# I2C.net
KiCad netlist of a schematic drawn in Altium Designer
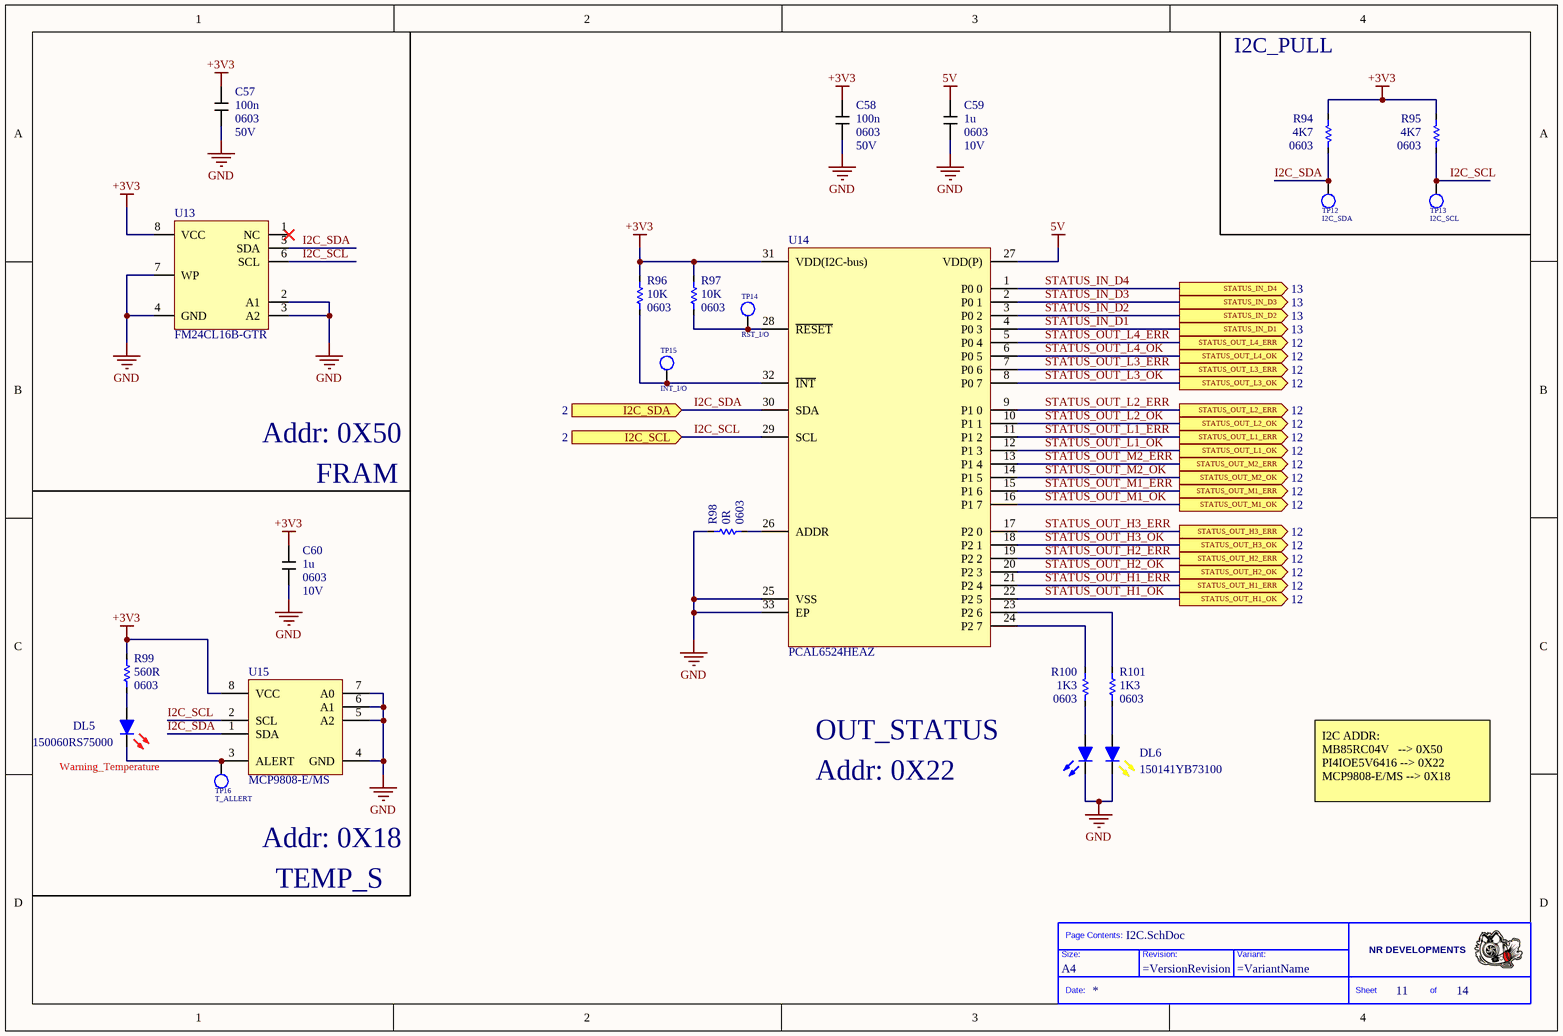
[diagram p0: I2C.SchDoc]

(export (version "E")
  (design (tool "Eeschema 10.0.6"))
  (components
    (comp (ref "C57")
      (value "100n")
      (footprint "CAPC1608X09M")
      (fields
        (field (name "CASE") "0603")
        (field (name "VOLTAGE") "50V")
        (field (name "MANUFACTURER") "KEMET")
        (field (name "PARTNUMBER") "C0603C104K5RACTU")
        (field (name "Comment") "CAP")
      )
      (libsource (lib "My_LIB") (part "CAP"))
    )
    (comp (ref "C58")
      (value "100n")
      (footprint "CAPC1608X09M")
      (fields
        (field (name "CASE") "0603")
        (field (name "VOLTAGE") "50V")
        (field (name "MANUFACTURER") "KEMET")
        (field (name "PARTNUMBER") "C0603C104K5RACTU")
        (field (name "Comment") "CAP")
      )
      (libsource (lib "My_LIB") (part "CAP"))
    )
    (comp (ref "C59")
      (value "1u")
      (footprint "CAPC1608X09M")
      (fields
        (field (name "CASE") "0603")
        (field (name "VOLTAGE") "10V")
        (field (name "MANUFACTURER") "KEMET")
        (field (name "PARTNUMBER") "C0603C105K8RACTU")
        (field (name "Comment") "CAP")
      )
      (libsource (lib "My_LIB") (part "CAP"))
    )
    (comp (ref "C60")
      (value "1u")
      (footprint "CAPC1608X09M")
      (fields
        (field (name "CASE") "0603")
        (field (name "VOLTAGE") "10V")
        (field (name "MANUFACTURER") "KEMET")
        (field (name "PARTNUMBER") "C0603C105K8RACTU")
        (field (name "Comment") "CAP")
      )
      (libsource (lib "My_LIB") (part "CAP"))
    )
    (comp (ref "DL5")
      (value "150060RS75000")
      (footprint "LED0603")
      (fields (field (name "MANUFACTURER") "Wurth Elektronik") (field (name "Comment") "LED_Red"))
      (libsource (lib "My_LIB") (part "LED_Red"))
    )
    (comp (ref "DL6")
      (value "150141YB73100")
      (footprint "WURTH-SBTW_3528")
      (description "Led Yellow - Blue 3528")
      (fields (field (name "MANUFACTURER") "Wurth") (field (name "Comment") "LED_Yellow_Blue"))
      (libsource (lib "My_LIB") (part "LED_Yellow_Blue"))
    )
    (comp (ref "R94")
      (value "4K7")
      (footprint "RESC1608X06M")
      (fields
        (field (name "CASE") "0603")
        (field (name "MANUFACTURER") "Vishay")
        (field (name "PARTNUMBER") "CRCW06034K70FKEB")
        (field (name "Comment") "Res")
      )
      (libsource (lib "My_LIB") (part "Resistor"))
    )
    (comp (ref "R95")
      (value "4K7")
      (footprint "RESC1608X06M")
      (fields
        (field (name "CASE") "0603")
        (field (name "MANUFACTURER") "Vishay")
        (field (name "PARTNUMBER") "CRCW06034K70FKEB")
        (field (name "Comment") "Res")
      )
      (libsource (lib "My_LIB") (part "Resistor"))
    )
    (comp (ref "R96")
      (value "10K")
      (footprint "RESC1608X06M")
      (fields
        (field (name "CASE") "0603")
        (field (name "MANUFACTURER") "Vishay")
        (field (name "PARTNUMBER") "CRCW060310K0FKEA")
        (field (name "Comment") "Res")
      )
      (libsource (lib "My_LIB") (part "Resistor"))
    )
    (comp (ref "R97")
      (value "10K")
      (footprint "RESC1608X06M")
      (fields
        (field (name "CASE") "0603")
        (field (name "MANUFACTURER") "Vishay")
        (field (name "PARTNUMBER") "CRCW060310K0FKEA")
        (field (name "Comment") "Res")
      )
      (libsource (lib "My_LIB") (part "Resistor"))
    )
    (comp (ref "R98")
      (value "0R")
      (footprint "RESC1608X06M")
      (fields
        (field (name "CASE") "0603")
        (field (name "MANUFACTURER") "Vishay")
        (field (name "PARTNUMBER") "CRCW06030000Z0EAC")
        (field (name "Comment") "Res")
      )
      (libsource (lib "My_LIB") (part "Resistor"))
    )
    (comp (ref "R99")
      (value "560R")
      (footprint "RESC1608X06M")
      (fields
        (field (name "CASE") "0603")
        (field (name "MANUFACTURER") "Vishay")
        (field (name "PARTNUMBER") "RC0603FR-07560RL")
        (field (name "Comment") "Res")
      )
      (libsource (lib "My_LIB") (part "Resistor"))
    )
    (comp (ref "R100")
      (value "1K3")
      (footprint "RESC1608X06M")
      (fields
        (field (name "CASE") "0603")
        (field (name "MANUFACTURER") "Vishay")
        (field (name "PARTNUMBER") "RC0603FR-071K3L")
        (field (name "Comment") "Res")
      )
      (libsource (lib "My_LIB") (part "Resistor"))
    )
    (comp (ref "R101")
      (value "1K3")
      (footprint "RESC1608X06M")
      (fields
        (field (name "CASE") "0603")
        (field (name "MANUFACTURER") "Vishay")
        (field (name "PARTNUMBER") "RC0603FR-071K3L")
        (field (name "Comment") "Res")
      )
      (libsource (lib "My_LIB") (part "Resistor"))
    )
    (comp (ref "TP12") (value "I2C_SDA") (footprint "TP_c200") (libsource (lib "My_LIB") (part "Test_Point")))
    (comp (ref "TP13") (value "I2C_SCL") (footprint "TP_c200") (libsource (lib "My_LIB") (part "Test_Point")))
    (comp (ref "TP14") (value "RST_I/O") (footprint "TP_c200") (libsource (lib "My_LIB") (part "Test_Point")))
    (comp (ref "TP15") (value "INT_I/O") (footprint "TP_c200") (libsource (lib "My_LIB") (part "Test_Point")))
    (comp (ref "TP16")
      (value "T_ALLERT")
      (footprint "TP_c200")
      (libsource (lib "My_LIB") (part "Test_Point"))
    )
    (comp (ref "U13")
      (value "FM24CL16B-GTR")
      (footprint "SOIC127P600X175-8N")
      (description "F-RAM 4kbit FRAM, I2C, 3.0V 5.5V - SOP8 T&R")
      (fields (field (name "MANUFACTURER") "Infineon Technologies") (field (name "Comment") "MB85RC04V"))
      (libsource (lib "My_LIB") (part "MB85RC04V"))
    )
    (comp (ref "U14")
      (value "PCAL6524HEAZ")
      (footprint "FP-SOT1426-1-IPC_A")
      (description "IC EXPANDER 24B 32HUQFN")
      (fields (field (name "MANUFACTURER") "NXP Semiconductors"))
      (libsource (lib "My_LIB") (part "PCAL6524HEAZ"))
    )
    (comp (ref "U15")
      (value "MCP9808-E/MS")
      (footprint "MCHP-MSOP-MS8_N")
      (fields (field (name "PARTNUMBER") "MCP9808-E/MS") (field (name "MANUFACTURER") "Microchip"))
      (libsource (lib "My_LIB") (part "MCP9808-E/MS"))
    )
  )
  (nets
    (net (code "1") (name "+3V3") (class "Default")
      (node (ref "C57") (pin "1") (pinfunction "1_1") (pintype "passive"))
      (node (ref "C58") (pin "1") (pinfunction "1_1") (pintype "passive"))
      (node (ref "C60") (pin "1") (pinfunction "1_1") (pintype "passive"))
      (node (ref "R94") (pin "2") (pinfunction "2_2") (pintype "passive"))
      (node (ref "R95") (pin "2") (pinfunction "2_2") (pintype "passive"))
      (node (ref "R96") (pin "2") (pinfunction "2_2") (pintype "passive"))
      (node (ref "R97") (pin "2") (pinfunction "2_2") (pintype "passive"))
      (node (ref "R99") (pin "2") (pinfunction "2_2") (pintype "passive"))
      (node (ref "U13") (pin "8") (pinfunction "VCC_8") (pintype "power_in"))
      (node (ref "U14") (pin "31") (pinfunction "VDD(I2C-bus)_31") (pintype "power_in"))
      (node (ref "U15") (pin "8") (pinfunction "VCC_8") (pintype "power_in"))
    )
    (net (code "2") (name "/I2C_SCL") (class "Default")
      (node (ref "R95") (pin "1") (pinfunction "1_1") (pintype "passive"))
      (node (ref "TP13") (pin "1") (pinfunction "1_1") (pintype "passive"))
      (node (ref "U13") (pin "6") (pinfunction "SCL_6") (pintype "passive"))
      (node (ref "U14") (pin "29") (pinfunction "SCL_29") (pintype "passive"))
      (node (ref "U15") (pin "2") (pinfunction "SCL_2") (pintype "passive"))
    )
    (net (code "3") (name "/I2C_SDA") (class "Default")
      (node (ref "R94") (pin "1") (pinfunction "1_1") (pintype "passive"))
      (node (ref "TP12") (pin "1") (pinfunction "1_1") (pintype "passive"))
      (node (ref "U13") (pin "5") (pinfunction "SDA_5") (pintype "passive"))
      (node (ref "U14") (pin "30") (pinfunction "SDA_30") (pintype "passive"))
      (node (ref "U15") (pin "1") (pinfunction "SDA_1") (pintype "passive"))
    )
    (net (code "4") (name "/STATUS_IN_D1") (class "Default")
      (node (ref "U14") (pin "4") (pinfunction "P0_3_4") (pintype "passive"))
    )
    (net (code "5") (name "/STATUS_IN_D2") (class "Default")
      (node (ref "U14") (pin "3") (pinfunction "P0_2_3") (pintype "passive"))
    )
    (net (code "6") (name "/STATUS_IN_D3") (class "Default")
      (node (ref "U14") (pin "2") (pinfunction "P0_1_2") (pintype "passive"))
    )
    (net (code "7") (name "/STATUS_IN_D4") (class "Default")
      (node (ref "U14") (pin "1") (pinfunction "P0_0_1") (pintype "passive"))
    )
    (net (code "8") (name "/STATUS_OUT_H1_ERR") (class "Default")
      (node (ref "U14") (pin "21") (pinfunction "P2_4_21") (pintype "passive"))
    )
    (net (code "9") (name "/STATUS_OUT_H1_OK") (class "Default")
      (node (ref "U14") (pin "22") (pinfunction "P2_5_22") (pintype "passive"))
    )
    (net (code "10") (name "/STATUS_OUT_H2_ERR") (class "Default")
      (node (ref "U14") (pin "19") (pinfunction "P2_2_19") (pintype "passive"))
    )
    (net (code "11") (name "/STATUS_OUT_H2_OK") (class "Default")
      (node (ref "U14") (pin "20") (pinfunction "P2_3_20") (pintype "passive"))
    )
    (net (code "12") (name "/STATUS_OUT_H3_ERR") (class "Default")
      (node (ref "U14") (pin "17") (pinfunction "P2_0_17") (pintype "passive"))
    )
    (net (code "13") (name "/STATUS_OUT_H3_OK") (class "Default")
      (node (ref "U14") (pin "18") (pinfunction "P2_1_18") (pintype "passive"))
    )
    (net (code "14") (name "/STATUS_OUT_L1_ERR") (class "Default")
      (node (ref "U14") (pin "11") (pinfunction "P1_2_11") (pintype "passive"))
    )
    (net (code "15") (name "/STATUS_OUT_L1_OK") (class "Default")
      (node (ref "U14") (pin "12") (pinfunction "P1_3_12") (pintype "passive"))
    )
    (net (code "16") (name "/STATUS_OUT_L2_ERR") (class "Default")
      (node (ref "U14") (pin "9") (pinfunction "P1_0_9") (pintype "passive"))
    )
    (net (code "17") (name "/STATUS_OUT_L2_OK") (class "Default")
      (node (ref "U14") (pin "10") (pinfunction "P1_1_10") (pintype "passive"))
    )
    (net (code "18") (name "/STATUS_OUT_L3_ERR") (class "Default")
      (node (ref "U14") (pin "7") (pinfunction "P0_6_7") (pintype "passive"))
    )
    (net (code "19") (name "/STATUS_OUT_L3_OK") (class "Default")
      (node (ref "U14") (pin "8") (pinfunction "P0_7_8") (pintype "passive"))
    )
    (net (code "20") (name "/STATUS_OUT_L4_ERR") (class "Default")
      (node (ref "U14") (pin "5") (pinfunction "P0_4_5") (pintype "passive"))
    )
    (net (code "21") (name "/STATUS_OUT_L4_OK") (class "Default")
      (node (ref "U14") (pin "6") (pinfunction "P0_5_6") (pintype "passive"))
    )
    (net (code "22") (name "/STATUS_OUT_M1_ERR") (class "Default")
      (node (ref "U14") (pin "15") (pinfunction "P1_6_15") (pintype "passive"))
    )
    (net (code "23") (name "/STATUS_OUT_M1_OK") (class "Default")
      (node (ref "U14") (pin "16") (pinfunction "P1_7_16") (pintype "passive"))
    )
    (net (code "24") (name "/STATUS_OUT_M2_ERR") (class "Default")
      (node (ref "U14") (pin "13") (pinfunction "P1_4_13") (pintype "passive"))
    )
    (net (code "25") (name "/STATUS_OUT_M2_OK") (class "Default")
      (node (ref "U14") (pin "14") (pinfunction "P1_5_14") (pintype "passive"))
    )
    (net (code "26") (name "5V") (class "Default")
      (node (ref "C59") (pin "1") (pinfunction "1_1") (pintype "passive"))
      (node (ref "U14") (pin "27") (pinfunction "VDD(P)_27") (pintype "power_in"))
    )
    (net (code "27") (name "GND") (class "Default")
      (node (ref "C57") (pin "2") (pinfunction "2_2") (pintype "passive"))
      (node (ref "C58") (pin "2") (pinfunction "2_2") (pintype "passive"))
      (node (ref "C59") (pin "2") (pinfunction "2_2") (pintype "passive"))
      (node (ref "C60") (pin "2") (pinfunction "2_2") (pintype "passive"))
      (node (ref "DL6") (pin "C1") (pinfunction "C1_C1") (pintype "passive"))
      (node (ref "DL6") (pin "C2") (pinfunction "C2_C2") (pintype "passive"))
      (node (ref "R98") (pin "2") (pinfunction "2_2") (pintype "passive"))
      (node (ref "U13") (pin "2") (pinfunction "A1_2") (pintype "passive"))
      (node (ref "U13") (pin "3") (pinfunction "A2_3") (pintype "passive"))
      (node (ref "U13") (pin "4") (pinfunction "GND_4") (pintype "power_in"))
      (node (ref "U13") (pin "7") (pinfunction "WP_7") (pintype "passive"))
      (node (ref "U14") (pin "25") (pinfunction "VSS_25") (pintype "power_in"))
      (node (ref "U14") (pin "33") (pinfunction "EP_33") (pintype "power_in"))
      (node (ref "U15") (pin "4") (pinfunction "GND_4") (pintype "power_in"))
      (node (ref "U15") (pin "5") (pinfunction "A2_5") (pintype "passive"))
      (node (ref "U15") (pin "6") (pinfunction "A1_6") (pintype "passive"))
      (node (ref "U15") (pin "7") (pinfunction "A0_7") (pintype "passive"))
    )
    (net (code "28") (name "Net-(DL5-PadA)") (class "Default")
      (node (ref "DL5") (pin "A") (pinfunction "A_A") (pintype "passive"))
      (node (ref "R99") (pin "1") (pinfunction "1_1") (pintype "passive"))
    )
    (net (code "29") (name "Net-(DL6-PadA1)") (class "Default")
      (node (ref "DL6") (pin "A1") (pinfunction "A1_A1") (pintype "passive"))
      (node (ref "R101") (pin "1") (pinfunction "1_1") (pintype "passive"))
    )
    (net (code "30") (name "Net-(DL6-PadA2)") (class "Default")
      (node (ref "DL6") (pin "A2") (pinfunction "A2_A2") (pintype "passive"))
      (node (ref "R100") (pin "1") (pinfunction "1_1") (pintype "passive"))
    )
    (net (code "31") (name "Net-(U14-ADDR)") (class "Default")
      (node (ref "R98") (pin "1") (pinfunction "1_1") (pintype "passive"))
      (node (ref "U14") (pin "26") (pinfunction "ADDR_26") (pintype "passive"))
    )
    (net (code "32") (name "Net-(U14-P2_6)") (class "Default")
      (node (ref "R101") (pin "2") (pinfunction "2_2") (pintype "passive"))
      (node (ref "U14") (pin "23") (pinfunction "P2_6_23") (pintype "passive"))
    )
    (net (code "33") (name "Net-(U14-P2_7)") (class "Default")
      (node (ref "R100") (pin "2") (pinfunction "2_2") (pintype "passive"))
      (node (ref "U14") (pin "24") (pinfunction "P2_7_24") (pintype "passive"))
    )
    (net (code "34") (name "Net-(U14-~{INT})") (class "Default")
      (node (ref "R96") (pin "1") (pinfunction "1_1") (pintype "passive"))
      (node (ref "TP15") (pin "1") (pinfunction "1_1") (pintype "passive"))
      (node (ref "U14") (pin "32") (pinfunction "~{INT}_32") (pintype "passive"))
    )
    (net (code "35") (name "Net-(U14-~{RESET})") (class "Default")
      (node (ref "R97") (pin "1") (pinfunction "1_1") (pintype "passive"))
      (node (ref "TP14") (pin "1") (pinfunction "1_1") (pintype "passive"))
      (node (ref "U14") (pin "28") (pinfunction "~{RESET}_28") (pintype "passive"))
    )
    (net (code "36") (name "Net-(U15-ALERT)") (class "Default")
      (node (ref "DL5") (pin "C") (pinfunction "C_C") (pintype "passive"))
      (node (ref "TP16") (pin "1") (pinfunction "1_1") (pintype "passive"))
      (node (ref "U15") (pin "3") (pinfunction "ALERT_3") (pintype "open_collector"))
    )
    (net (code "37") (name "unconnected-(U13-NC-Pad1)") (class "Default")
      (node (ref "U13") (pin "1") (pinfunction "NC_1") (pintype "passive+no_connect"))
    )
  )
)
